# Dashboard_rev2.net
KiCad netlist of a schematic drawn in EAGLE
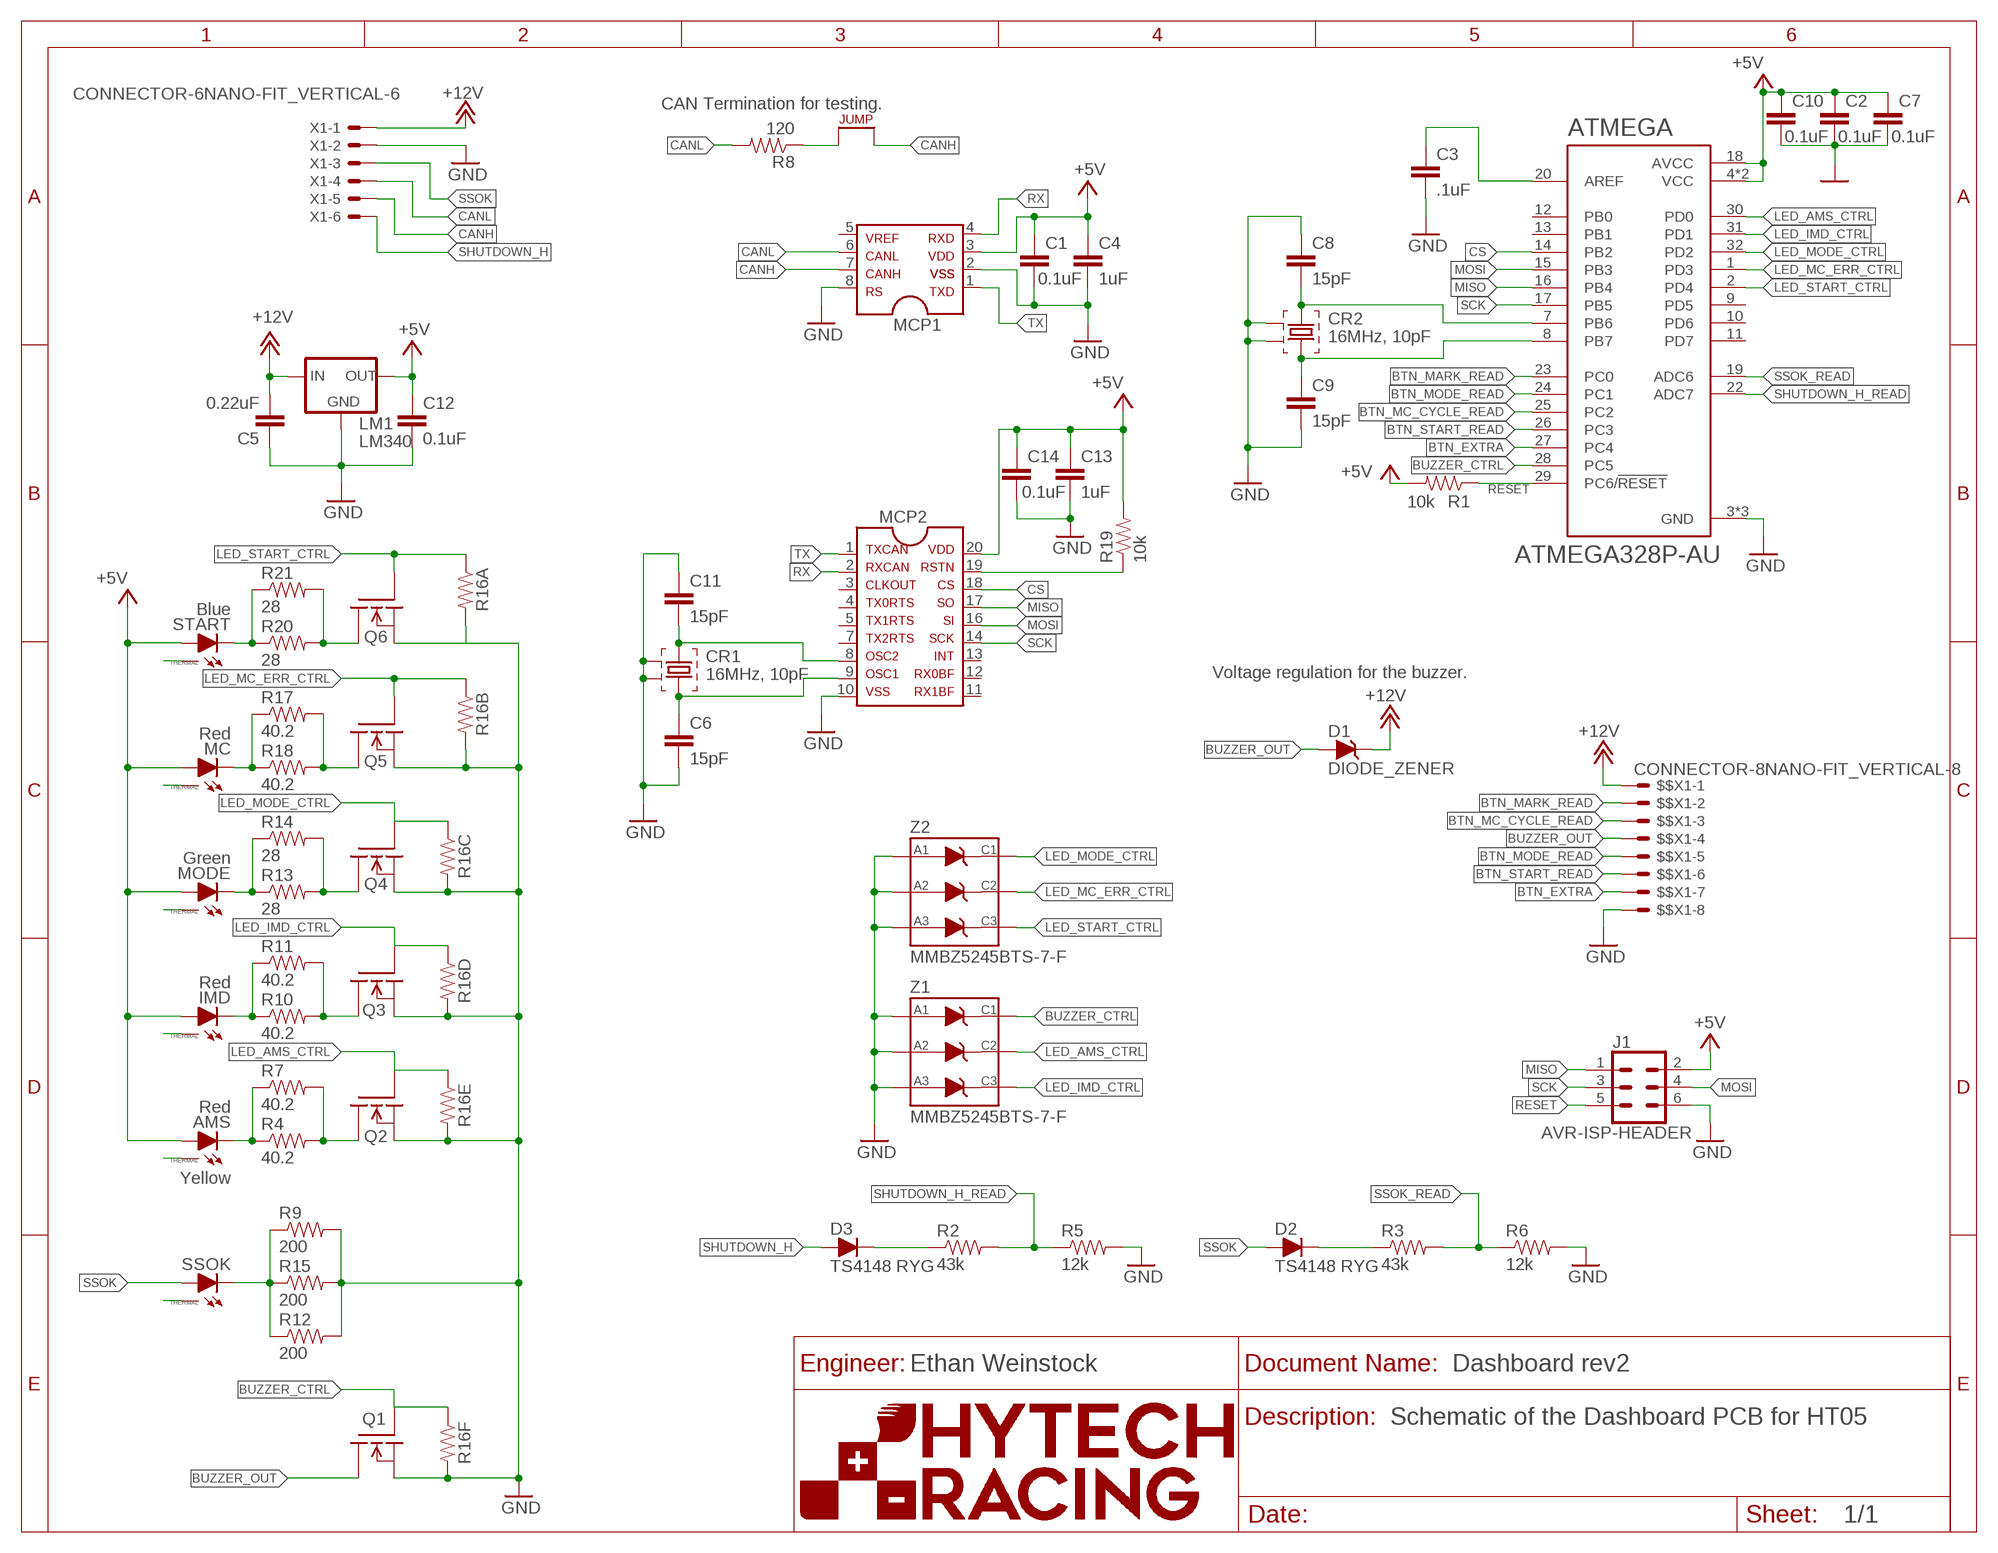
[diagram p0: schematic, sheet 1]

(export (version "E")
  (design (tool "Eeschema 10.0.6"))
  (components
    (comp (ref "$$X1")
      (value "CONNECTOR-8NANO-FIT_VERTICAL-8")
      (footprint "eagle-import:NANO-FIT_VERTICAL-8")
      (libsource (lib "eagle-import") (part "CONNECTOR-8NANO-FIT_VERTICAL-8"))
    )
    (comp (ref "AMS")
      (value "Red")
      (footprint "eagle-import:XP-E2")
      (libsource (lib "eagle-import") (part "XP-E2XP-E2"))
    )
    (comp (ref "ATMEGA")
      (value "ATMEGA328P-AU")
      (footprint "eagle-import:QFP80P900X900X120-32N")
      (fields (field (name "MF") "Microchip"))
      (libsource (lib "eagle-import") (part "ATMEGA328P-AU"))
    )
    (comp (ref "C1")
      (value "0.1uF")
      (footprint "eagle-import:0603-CAP")
      (libsource (lib "eagle-import") (part "CAP0603-CAP"))
    )
    (comp (ref "C2")
      (value "0.1uF")
      (footprint "eagle-import:0603-CAP")
      (libsource (lib "eagle-import") (part "CAP0603-CAP"))
    )
    (comp (ref "C3")
      (value ".1uF")
      (footprint "eagle-import:0603-CAP")
      (libsource (lib "eagle-import") (part "CAP0603-CAP"))
    )
    (comp (ref "C4")
      (value "1uF")
      (footprint "eagle-import:0603-CAP")
      (libsource (lib "eagle-import") (part "CAP0603-CAP"))
    )
    (comp (ref "C5")
      (value "0.22uF")
      (footprint "eagle-import:0603-CAP")
      (libsource (lib "eagle-import") (part "CAP0603-CAP"))
    )
    (comp (ref "C6")
      (value "15pF")
      (footprint "eagle-import:0603-CAP")
      (libsource (lib "eagle-import") (part "CAP0603-CAP"))
    )
    (comp (ref "C7")
      (value "0.1uF")
      (footprint "eagle-import:0603-CAP")
      (libsource (lib "eagle-import") (part "CAP0603-CAP"))
    )
    (comp (ref "C8")
      (value "15pF")
      (footprint "eagle-import:0603-CAP")
      (libsource (lib "eagle-import") (part "CAP0603-CAP"))
    )
    (comp (ref "C9")
      (value "15pF")
      (footprint "eagle-import:0603-CAP")
      (libsource (lib "eagle-import") (part "CAP0603-CAP"))
    )
    (comp (ref "C10")
      (value "0.1uF")
      (footprint "eagle-import:0603-CAP")
      (libsource (lib "eagle-import") (part "CAP0603-CAP"))
    )
    (comp (ref "C11")
      (value "15pF")
      (footprint "eagle-import:0603-CAP")
      (libsource (lib "eagle-import") (part "CAP0603-CAP"))
    )
    (comp (ref "C12")
      (value "0.1uF")
      (footprint "eagle-import:0603-CAP")
      (libsource (lib "eagle-import") (part "CAP0603-CAP"))
    )
    (comp (ref "C13")
      (value "1uF")
      (footprint "eagle-import:0603-CAP")
      (libsource (lib "eagle-import") (part "CAP0603-CAP"))
    )
    (comp (ref "C14")
      (value "0.1uF")
      (footprint "eagle-import:0603-CAP")
      (libsource (lib "eagle-import") (part "CAP0603-CAP"))
    )
    (comp (ref "CR1")
      (value "16MHz, 10pF")
      (footprint "eagle-import:ABM3B")
      (libsource (lib "eagle-import") (part "ABM3B"))
    )
    (comp (ref "CR2")
      (value "16MHz, 10pF")
      (footprint "eagle-import:ABM3B")
      (libsource (lib "eagle-import") (part "ABM3B"))
    )
    (comp (ref "D1")
      (value "DIODE_ZENER")
      (footprint "eagle-import:SOT23")
      (libsource (lib "eagle-import") (part "DIODE_ZENER"))
    )
    (comp (ref "D2")
      (value "TS4148 RYG")
      (footprint "eagle-import:0805_D")
      (libsource (lib "eagle-import") (part "DIODE0805"))
    )
    (comp (ref "D3")
      (value "TS4148 RYG")
      (footprint "eagle-import:0805_D")
      (libsource (lib "eagle-import") (part "DIODE0805"))
    )
    (comp (ref "IMD")
      (value "Red")
      (footprint "eagle-import:XP-E2")
      (libsource (lib "eagle-import") (part "XP-E2XP-E2"))
    )
    (comp (ref "J1")
      (value "AVR-ISP-HEADER")
      (footprint "eagle-import:2X03")
      (libsource (lib "eagle-import") (part "AVR-ISP-HEADER"))
    )
    (comp (ref "J2")
      (value "JUMPER0603")
      (footprint "eagle-import:0603-JUMP")
      (libsource (lib "eagle-import") (part "JUMPER0603"))
    )
    (comp (ref "LM1")
      (value "LM340")
      (footprint "eagle-import:SOT223")
      (libsource (lib "eagle-import") (part "LM340"))
    )
    (comp (ref "MC")
      (value "Red")
      (footprint "eagle-import:XP-E2")
      (libsource (lib "eagle-import") (part "XP-E2XP-E2"))
    )
    (comp (ref "MCP1")
      (value "MCP2551")
      (footprint "eagle-import:SOIC-08")
      (libsource (lib "eagle-import") (part "MCP2551"))
    )
    (comp (ref "MCP2")
      (value "MCP2515TSSOP")
      (footprint "eagle-import:TSSOP-20")
      (libsource (lib "eagle-import") (part "MCP2515TSSOP"))
    )
    (comp (ref "MODE")
      (value "Green")
      (footprint "eagle-import:XP-E2")
      (libsource (lib "eagle-import") (part "XP-E2XP-E2"))
    )
    (comp (ref "Q1")
      (value "DMG3406LSOT")
      (footprint "eagle-import:SOT23")
      (libsource (lib "eagle-import") (part "DMG3406LSOT"))
    )
    (comp (ref "Q2")
      (value "DMG3406LSOT")
      (footprint "eagle-import:SOT23")
      (libsource (lib "eagle-import") (part "DMG3406LSOT"))
    )
    (comp (ref "Q3")
      (value "DMG3406LSOT")
      (footprint "eagle-import:SOT23")
      (libsource (lib "eagle-import") (part "DMG3406LSOT"))
    )
    (comp (ref "Q4")
      (value "DMG3406LSOT")
      (footprint "eagle-import:SOT23")
      (libsource (lib "eagle-import") (part "DMG3406LSOT"))
    )
    (comp (ref "Q5")
      (value "DMG3406LSOT")
      (footprint "eagle-import:SOT23")
      (libsource (lib "eagle-import") (part "DMG3406LSOT"))
    )
    (comp (ref "Q6")
      (value "DMG3406LSOT")
      (footprint "eagle-import:SOT23")
      (libsource (lib "eagle-import") (part "DMG3406LSOT"))
    )
    (comp (ref "R1")
      (value "10k")
      (footprint "eagle-import:0603-RES")
      (libsource (lib "eagle-import") (part "RESISTOR0603"))
    )
    (comp (ref "R2")
      (value "43k")
      (footprint "eagle-import:0603-RES")
      (libsource (lib "eagle-import") (part "RESISTOR0603"))
    )
    (comp (ref "R3")
      (value "43k")
      (footprint "eagle-import:0603-RES")
      (libsource (lib "eagle-import") (part "RESISTOR0603"))
    )
    (comp (ref "R4")
      (value "40.2")
      (footprint "eagle-import:0603-RES")
      (libsource (lib "eagle-import") (part "RESISTOR0603"))
    )
    (comp (ref "R5")
      (value "12k")
      (footprint "eagle-import:0603-RES")
      (libsource (lib "eagle-import") (part "RESISTOR0603"))
    )
    (comp (ref "R6")
      (value "12k")
      (footprint "eagle-import:0603-RES")
      (libsource (lib "eagle-import") (part "RESISTOR0603"))
    )
    (comp (ref "R7")
      (value "40.2")
      (footprint "eagle-import:0603-RES")
      (libsource (lib "eagle-import") (part "RESISTOR0603"))
    )
    (comp (ref "R8")
      (value "120")
      (footprint "eagle-import:0603-RES")
      (libsource (lib "eagle-import") (part "RESISTOR0603-RES"))
    )
    (comp (ref "R9")
      (value "200")
      (footprint "eagle-import:0805")
      (libsource (lib "eagle-import") (part "RESISTOR0805-RES"))
    )
    (comp (ref "R10")
      (value "40.2")
      (footprint "eagle-import:0603-RES")
      (libsource (lib "eagle-import") (part "RESISTOR0603"))
    )
    (comp (ref "R11")
      (value "40.2")
      (footprint "eagle-import:0603-RES")
      (libsource (lib "eagle-import") (part "RESISTOR0603"))
    )
    (comp (ref "R12")
      (value "200")
      (footprint "eagle-import:0805")
      (libsource (lib "eagle-import") (part "RESISTOR0805-RES"))
    )
    (comp (ref "R13")
      (value "28")
      (footprint "eagle-import:0603-RES")
      (libsource (lib "eagle-import") (part "RESISTOR0603"))
    )
    (comp (ref "R14")
      (value "28")
      (footprint "eagle-import:0603-RES")
      (libsource (lib "eagle-import") (part "RESISTOR0603"))
    )
    (comp (ref "R15")
      (value "200")
      (footprint "eagle-import:0805")
      (libsource (lib "eagle-import") (part "RESISTOR0805-RES"))
    )
    (comp (ref "R16")
      (value "10k")
      (footprint "eagle-import:YAG_YC248-M")
      (fields (field (name "MANUFACTURER_PART_NUMBER") "YC248-JR-0710KL"))
      (libsource (lib "eagle-import") (part "YC248-JR-0710KL"))
    )
    (comp (ref "R17")
      (value "40.2")
      (footprint "eagle-import:0603-RES")
      (libsource (lib "eagle-import") (part "RESISTOR0603"))
    )
    (comp (ref "R18")
      (value "40.2")
      (footprint "eagle-import:0603-RES")
      (libsource (lib "eagle-import") (part "RESISTOR0603"))
    )
    (comp (ref "R19")
      (value "10k")
      (footprint "eagle-import:0603-RES")
      (libsource (lib "eagle-import") (part "RESISTOR0603"))
    )
    (comp (ref "R20")
      (value "28")
      (footprint "eagle-import:0603-RES")
      (libsource (lib "eagle-import") (part "RESISTOR0603"))
    )
    (comp (ref "R21")
      (value "28")
      (footprint "eagle-import:0603-RES")
      (libsource (lib "eagle-import") (part "RESISTOR0603"))
    )
    (comp (ref "SSOK")
      (value "Yellow")
      (footprint "eagle-import:XP-E2")
      (libsource (lib "eagle-import") (part "XP-E2XP-E2"))
    )
    (comp (ref "START")
      (value "Blue")
      (footprint "eagle-import:XP-E2")
      (libsource (lib "eagle-import") (part "XP-E2XP-E2"))
    )
    (comp (ref "X1")
      (value "CONNECTOR-6NANO-FIT_VERTICAL-6")
      (footprint "eagle-import:NANO-FIT_VERTICAL-6")
      (libsource (lib "eagle-import") (part "CONNECTOR-6NANO-FIT_VERTICAL-6"))
    )
    (comp (ref "Z1")
      (value "MMBZ5245BTS-7-F")
      (footprint "eagle-import:SOT363")
      (fields (field (name "VOLTAGE") "15V"))
      (libsource (lib "eagle-import") (part "MMBZ5245BTS-7-F"))
    )
    (comp (ref "Z2")
      (value "MMBZ5245BTS-7-F")
      (footprint "eagle-import:SOT363")
      (fields (field (name "VOLTAGE") "15V"))
      (libsource (lib "eagle-import") (part "MMBZ5245BTS-7-F"))
    )
  )
  (nets
    (net (code "1") (name "+5V") (class "Default")
      (node (ref "AMS") (pin "A") (pinfunction "A_A") (pintype "passive"))
      (node (ref "ATMEGA") (pin "18") (pinfunction "AVCC_18") (pintype "power_in"))
      (node (ref "ATMEGA") (pin "4") (pinfunction "VCC_4") (pintype "power_in"))
      (node (ref "ATMEGA") (pin "6") (pinfunction "VCC_6") (pintype "power_in"))
      (node (ref "C1") (pin "1") (pinfunction "1_1") (pintype "passive"))
      (node (ref "C10") (pin "1") (pinfunction "1_1") (pintype "passive"))
      (node (ref "C12") (pin "1") (pinfunction "1_1") (pintype "passive"))
      (node (ref "C13") (pin "1") (pinfunction "1_1") (pintype "passive"))
      (node (ref "C14") (pin "1") (pinfunction "1_1") (pintype "passive"))
      (node (ref "C2") (pin "1") (pinfunction "1_1") (pintype "passive"))
      (node (ref "C4") (pin "1") (pinfunction "1_1") (pintype "passive"))
      (node (ref "C7") (pin "1") (pinfunction "1_1") (pintype "passive"))
      (node (ref "IMD") (pin "A") (pinfunction "A_A") (pintype "passive"))
      (node (ref "J1") (pin "2") (pinfunction "2_2") (pintype "passive"))
      (node (ref "LM1") (pin "3") (pinfunction "OUT_3") (pintype "output"))
      (node (ref "MC") (pin "A") (pinfunction "A_A") (pintype "passive"))
      (node (ref "MCP1") (pin "3") (pinfunction "3_3") (pintype "passive"))
      (node (ref "MCP2") (pin "20") (pinfunction "VDD_20") (pintype "passive"))
      (node (ref "MODE") (pin "A") (pinfunction "A_A") (pintype "passive"))
      (node (ref "R1") (pin "2") (pinfunction "2_2") (pintype "passive"))
      (node (ref "R19") (pin "2") (pinfunction "2_2") (pintype "passive"))
      (node (ref "START") (pin "A") (pinfunction "A_A") (pintype "passive"))
    )
    (net (code "2") (name "+12V") (class "Default")
      (node (ref "$$X1") (pin "P$1") (pinfunction "S_P$1") (pintype "passive"))
      (node (ref "C5") (pin "2") (pinfunction "2_2") (pintype "passive"))
      (node (ref "D1") (pin "3") (pinfunction "C_3") (pintype "passive"))
      (node (ref "LM1") (pin "1") (pinfunction "IN_1") (pintype "input"))
      (node (ref "X1") (pin "P$1") (pinfunction "S_P$1") (pintype "passive"))
    )
    (net (code "3") (name "/THERMAL") (class "Default")
      (node (ref "AMS") (pin "X") (pinfunction "X_X") (pintype "passive"))
      (node (ref "IMD") (pin "X") (pinfunction "X_X") (pintype "passive"))
      (node (ref "MC") (pin "X") (pinfunction "X_X") (pintype "passive"))
      (node (ref "MODE") (pin "X") (pinfunction "X_X") (pintype "passive"))
      (node (ref "SSOK") (pin "X") (pinfunction "X_X") (pintype "passive"))
      (node (ref "START") (pin "X") (pinfunction "X_X") (pintype "passive"))
    )
    (net (code "4") (name "BTN_EXTRA") (class "Default")
      (node (ref "$$X1") (pin "P$7") (pinfunction "S_P$7") (pintype "passive"))
      (node (ref "ATMEGA") (pin "27") (pinfunction "PC4_27") (pintype "bidirectional"))
    )
    (net (code "5") (name "BTN_MARK_READ") (class "Default")
      (node (ref "$$X1") (pin "P$2") (pinfunction "S_P$2") (pintype "passive"))
      (node (ref "ATMEGA") (pin "23") (pinfunction "PC0_23") (pintype "bidirectional"))
    )
    (net (code "6") (name "BTN_MC_CYCLE_READ") (class "Default")
      (node (ref "$$X1") (pin "P$3") (pinfunction "S_P$3") (pintype "passive"))
      (node (ref "ATMEGA") (pin "25") (pinfunction "PC2_25") (pintype "bidirectional"))
    )
    (net (code "7") (name "BTN_MODE_READ") (class "Default")
      (node (ref "$$X1") (pin "P$5") (pinfunction "S_P$5") (pintype "passive"))
      (node (ref "ATMEGA") (pin "24") (pinfunction "PC1_24") (pintype "bidirectional"))
    )
    (net (code "8") (name "BTN_START_READ") (class "Default")
      (node (ref "$$X1") (pin "P$6") (pinfunction "S_P$6") (pintype "passive"))
      (node (ref "ATMEGA") (pin "26") (pinfunction "PC3_26") (pintype "bidirectional"))
    )
    (net (code "9") (name "BUZZER_CTRL") (class "Default")
      (node (ref "ATMEGA") (pin "28") (pinfunction "PC5_28") (pintype "bidirectional"))
      (node (ref "Q1") (pin "1") (pinfunction "G_1") (pintype "passive"))
      (node (ref "R16") (pin "6") (pinfunction "1_6") (pintype "passive"))
      (node (ref "Z1") (pin "P$4") (pinfunction "C1_P$4") (pintype "bidirectional"))
    )
    (net (code "10") (name "BUZZER_OUT") (class "Default")
      (node (ref "$$X1") (pin "P$4") (pinfunction "S_P$4") (pintype "passive"))
      (node (ref "D1") (pin "1") (pinfunction "A_1") (pintype "passive"))
      (node (ref "Q1") (pin "3") (pinfunction "D_3") (pintype "passive"))
    )
    (net (code "11") (name "CANH") (class "Default")
      (node (ref "J2") (pin "2") (pinfunction "P$2_2") (pintype "bidirectional"))
      (node (ref "MCP1") (pin "7") (pinfunction "7_7") (pintype "passive"))
      (node (ref "X1") (pin "P$5") (pinfunction "S_P$5") (pintype "passive"))
    )
    (net (code "12") (name "CANL") (class "Default")
      (node (ref "MCP1") (pin "6") (pinfunction "6_6") (pintype "passive"))
      (node (ref "R8") (pin "2") (pinfunction "2_2") (pintype "passive"))
      (node (ref "X1") (pin "P$4") (pinfunction "S_P$4") (pintype "passive"))
    )
    (net (code "13") (name "CS") (class "Default")
      (node (ref "ATMEGA") (pin "14") (pinfunction "PB2_14") (pintype "bidirectional"))
      (node (ref "MCP2") (pin "18") (pinfunction "CS_18") (pintype "passive"))
    )
    (net (code "14") (name "GND") (class "Default")
      (node (ref "$$X1") (pin "P$8") (pinfunction "S_P$8") (pintype "passive"))
      (node (ref "ATMEGA") (pin "21") (pinfunction "GND_21") (pintype "power_in"))
      (node (ref "ATMEGA") (pin "3") (pinfunction "GND_3") (pintype "power_in"))
      (node (ref "ATMEGA") (pin "5") (pinfunction "GND_5") (pintype "power_in"))
      (node (ref "C1") (pin "2") (pinfunction "2_2") (pintype "passive"))
      (node (ref "C10") (pin "2") (pinfunction "2_2") (pintype "passive"))
      (node (ref "C11") (pin "1") (pinfunction "1_1") (pintype "passive"))
      (node (ref "C12") (pin "2") (pinfunction "2_2") (pintype "passive"))
      (node (ref "C13") (pin "2") (pinfunction "2_2") (pintype "passive"))
      (node (ref "C14") (pin "2") (pinfunction "2_2") (pintype "passive"))
      (node (ref "C2") (pin "2") (pinfunction "2_2") (pintype "passive"))
      (node (ref "C3") (pin "2") (pinfunction "2_2") (pintype "passive"))
      (node (ref "C4") (pin "2") (pinfunction "2_2") (pintype "passive"))
      (node (ref "C5") (pin "1") (pinfunction "1_1") (pintype "passive"))
      (node (ref "C6") (pin "2") (pinfunction "2_2") (pintype "passive"))
      (node (ref "C7") (pin "2") (pinfunction "2_2") (pintype "passive"))
      (node (ref "C8") (pin "1") (pinfunction "1_1") (pintype "passive"))
      (node (ref "C9") (pin "2") (pinfunction "2_2") (pintype "passive"))
      (node (ref "CR1") (pin "GND") (pinfunction "GND_GND") (pintype "passive"))
      (node (ref "CR1") (pin "GND2") (pinfunction "GND2_GND2") (pintype "passive"))
      (node (ref "CR2") (pin "GND") (pinfunction "GND_GND") (pintype "passive"))
      (node (ref "CR2") (pin "GND2") (pinfunction "GND2_GND2") (pintype "passive"))
      (node (ref "J1") (pin "6") (pinfunction "6_6") (pintype "passive"))
      (node (ref "LM1") (pin "2") (pinfunction "GND_2") (pintype "input"))
      (node (ref "LM1") (pin "4") (pinfunction "GND_4") (pintype "input"))
      (node (ref "MCP1") (pin "2") (pinfunction "2_2") (pintype "passive"))
      (node (ref "MCP1") (pin "8") (pinfunction "8_8") (pintype "passive"))
      (node (ref "MCP2") (pin "10") (pinfunction "VSS_10") (pintype "passive"))
      (node (ref "Q1") (pin "2") (pinfunction "S_2") (pintype "passive"))
      (node (ref "Q2") (pin "2") (pinfunction "S_2") (pintype "passive"))
      (node (ref "Q3") (pin "2") (pinfunction "S_2") (pintype "passive"))
      (node (ref "Q4") (pin "2") (pinfunction "S_2") (pintype "passive"))
      (node (ref "Q5") (pin "2") (pinfunction "S_2") (pintype "passive"))
      (node (ref "Q6") (pin "2") (pinfunction "S_2") (pintype "passive"))
      (node (ref "R12") (pin "2") (pinfunction "2_2") (pintype "passive"))
      (node (ref "R15") (pin "2") (pinfunction "2_2") (pintype "passive"))
      (node (ref "R16") (pin "11") (pinfunction "2_11") (pintype "passive"))
      (node (ref "R16") (pin "12") (pinfunction "2_12") (pintype "passive"))
      (node (ref "R16") (pin "13") (pinfunction "2_13") (pintype "passive"))
      (node (ref "R16") (pin "14") (pinfunction "2_14") (pintype "passive"))
      (node (ref "R16") (pin "15") (pinfunction "2_15") (pintype "passive"))
      (node (ref "R16") (pin "16") (pinfunction "2_16") (pintype "passive"))
      (node (ref "R5") (pin "2") (pinfunction "2_2") (pintype "passive"))
      (node (ref "R6") (pin "2") (pinfunction "2_2") (pintype "passive"))
      (node (ref "R9") (pin "2") (pinfunction "2_2") (pintype "passive"))
      (node (ref "X1") (pin "P$2") (pinfunction "S_P$2") (pintype "passive"))
      (node (ref "Z1") (pin "P$1") (pinfunction "A1_P$1") (pintype "bidirectional"))
      (node (ref "Z1") (pin "P$2") (pinfunction "A2_P$2") (pintype "bidirectional"))
      (node (ref "Z1") (pin "P$3") (pinfunction "A3_P$3") (pintype "bidirectional"))
      (node (ref "Z2") (pin "P$1") (pinfunction "A1_P$1") (pintype "bidirectional"))
      (node (ref "Z2") (pin "P$2") (pinfunction "A2_P$2") (pintype "bidirectional"))
      (node (ref "Z2") (pin "P$3") (pinfunction "A3_P$3") (pintype "bidirectional"))
    )
    (net (code "15") (name "LED_AMS_CTRL") (class "Default")
      (node (ref "ATMEGA") (pin "30") (pinfunction "PD0_30") (pintype "bidirectional"))
      (node (ref "Q2") (pin "1") (pinfunction "G_1") (pintype "passive"))
      (node (ref "R16") (pin "5") (pinfunction "1_5") (pintype "passive"))
      (node (ref "Z1") (pin "P$5") (pinfunction "C2_P$5") (pintype "bidirectional"))
    )
    (net (code "16") (name "LED_IMD_CTRL") (class "Default")
      (node (ref "ATMEGA") (pin "31") (pinfunction "PD1_31") (pintype "bidirectional"))
      (node (ref "Q3") (pin "1") (pinfunction "G_1") (pintype "passive"))
      (node (ref "R16") (pin "4") (pinfunction "1_4") (pintype "passive"))
      (node (ref "Z1") (pin "P$6") (pinfunction "C3_P$6") (pintype "bidirectional"))
    )
    (net (code "17") (name "LED_MC_ERR_CTRL") (class "Default")
      (node (ref "ATMEGA") (pin "1") (pinfunction "PD3_1") (pintype "bidirectional"))
      (node (ref "Q5") (pin "1") (pinfunction "G_1") (pintype "passive"))
      (node (ref "R16") (pin "2") (pinfunction "1_2") (pintype "passive"))
      (node (ref "Z2") (pin "P$5") (pinfunction "C2_P$5") (pintype "bidirectional"))
    )
    (net (code "18") (name "LED_MODE_CTRL") (class "Default")
      (node (ref "ATMEGA") (pin "32") (pinfunction "PD2_32") (pintype "bidirectional"))
      (node (ref "Q4") (pin "1") (pinfunction "G_1") (pintype "passive"))
      (node (ref "R16") (pin "3") (pinfunction "1_3") (pintype "passive"))
      (node (ref "Z2") (pin "P$4") (pinfunction "C1_P$4") (pintype "bidirectional"))
    )
    (net (code "19") (name "LED_START_CTRL") (class "Default")
      (node (ref "ATMEGA") (pin "2") (pinfunction "PD4_2") (pintype "bidirectional"))
      (node (ref "Q6") (pin "1") (pinfunction "G_1") (pintype "passive"))
      (node (ref "R16") (pin "1") (pinfunction "1_1") (pintype "passive"))
      (node (ref "Z2") (pin "P$6") (pinfunction "C3_P$6") (pintype "bidirectional"))
    )
    (net (code "20") (name "MISO") (class "Default")
      (node (ref "ATMEGA") (pin "16") (pinfunction "PB4_16") (pintype "bidirectional"))
      (node (ref "J1") (pin "1") (pinfunction "1_1") (pintype "passive"))
      (node (ref "MCP2") (pin "17") (pinfunction "SO_17") (pintype "passive"))
    )
    (net (code "21") (name "MOSI") (class "Default")
      (node (ref "ATMEGA") (pin "15") (pinfunction "PB3_15") (pintype "bidirectional"))
      (node (ref "J1") (pin "4") (pinfunction "4_4") (pintype "passive"))
      (node (ref "MCP2") (pin "16") (pinfunction "SI_16") (pintype "passive"))
    )
    (net (code "22") (name "Net-(AMS-PadC)") (class "Default")
      (node (ref "AMS") (pin "C") (pinfunction "C_C") (pintype "passive"))
      (node (ref "R4") (pin "1") (pinfunction "1_1") (pintype "passive"))
      (node (ref "R7") (pin "1") (pinfunction "1_1") (pintype "passive"))
    )
    (net (code "23") (name "Net-(ATMEGA-AREF)") (class "Default")
      (node (ref "ATMEGA") (pin "20") (pinfunction "AREF_20") (pintype "input"))
      (node (ref "C3") (pin "1") (pinfunction "1_1") (pintype "passive"))
    )
    (net (code "24") (name "Net-(ATMEGA-PB6)") (class "Default")
      (node (ref "ATMEGA") (pin "7") (pinfunction "PB6_7") (pintype "bidirectional"))
      (node (ref "C8") (pin "2") (pinfunction "2_2") (pintype "passive"))
      (node (ref "CR2") (pin "1") (pinfunction "1_1") (pintype "passive"))
    )
    (net (code "25") (name "Net-(ATMEGA-PB7)") (class "Default")
      (node (ref "ATMEGA") (pin "8") (pinfunction "PB7_8") (pintype "bidirectional"))
      (node (ref "C9") (pin "1") (pinfunction "1_1") (pintype "passive"))
      (node (ref "CR2") (pin "3") (pinfunction "3_3") (pintype "passive"))
    )
    (net (code "26") (name "Net-(D2-PadC)") (class "Default")
      (node (ref "D2") (pin "C") (pinfunction "C_C") (pintype "passive"))
      (node (ref "R3") (pin "1") (pinfunction "1_1") (pintype "passive"))
    )
    (net (code "27") (name "Net-(D3-PadC)") (class "Default")
      (node (ref "D3") (pin "C") (pinfunction "C_C") (pintype "passive"))
      (node (ref "R2") (pin "1") (pinfunction "1_1") (pintype "passive"))
    )
    (net (code "28") (name "Net-(IMD-PadC)") (class "Default")
      (node (ref "IMD") (pin "C") (pinfunction "C_C") (pintype "passive"))
      (node (ref "R10") (pin "1") (pinfunction "1_1") (pintype "passive"))
      (node (ref "R11") (pin "1") (pinfunction "1_1") (pintype "passive"))
    )
    (net (code "29") (name "Net-(J2-P$1)") (class "Default")
      (node (ref "J2") (pin "1") (pinfunction "P$1_1") (pintype "bidirectional"))
      (node (ref "R8") (pin "1") (pinfunction "1_1") (pintype "passive"))
    )
    (net (code "30") (name "Net-(MC-PadC)") (class "Default")
      (node (ref "MC") (pin "C") (pinfunction "C_C") (pintype "passive"))
      (node (ref "R17") (pin "1") (pinfunction "1_1") (pintype "passive"))
      (node (ref "R18") (pin "1") (pinfunction "1_1") (pintype "passive"))
    )
    (net (code "31") (name "Net-(MCP2-OSC1)") (class "Default")
      (node (ref "C6") (pin "1") (pinfunction "1_1") (pintype "passive"))
      (node (ref "CR1") (pin "3") (pinfunction "3_3") (pintype "passive"))
      (node (ref "MCP2") (pin "9") (pinfunction "OSC1_9") (pintype "passive"))
    )
    (net (code "32") (name "Net-(MCP2-OSC2)") (class "Default")
      (node (ref "C11") (pin "2") (pinfunction "2_2") (pintype "passive"))
      (node (ref "CR1") (pin "1") (pinfunction "1_1") (pintype "passive"))
      (node (ref "MCP2") (pin "8") (pinfunction "OSC2_8") (pintype "passive"))
    )
    (net (code "33") (name "Net-(MCP2-RSTN)") (class "Default")
      (node (ref "MCP2") (pin "19") (pinfunction "RSTN_19") (pintype "passive"))
      (node (ref "R19") (pin "1") (pinfunction "1_1") (pintype "passive"))
    )
    (net (code "34") (name "Net-(MODE-PadC)") (class "Default")
      (node (ref "MODE") (pin "C") (pinfunction "C_C") (pintype "passive"))
      (node (ref "R13") (pin "1") (pinfunction "1_1") (pintype "passive"))
      (node (ref "R14") (pin "1") (pinfunction "1_1") (pintype "passive"))
    )
    (net (code "35") (name "Net-(Q2-D)") (class "Default")
      (node (ref "Q2") (pin "3") (pinfunction "D_3") (pintype "passive"))
      (node (ref "R4") (pin "2") (pinfunction "2_2") (pintype "passive"))
      (node (ref "R7") (pin "2") (pinfunction "2_2") (pintype "passive"))
    )
    (net (code "36") (name "Net-(Q3-D)") (class "Default")
      (node (ref "Q3") (pin "3") (pinfunction "D_3") (pintype "passive"))
      (node (ref "R10") (pin "2") (pinfunction "2_2") (pintype "passive"))
      (node (ref "R11") (pin "2") (pinfunction "2_2") (pintype "passive"))
    )
    (net (code "37") (name "Net-(Q4-D)") (class "Default")
      (node (ref "Q4") (pin "3") (pinfunction "D_3") (pintype "passive"))
      (node (ref "R13") (pin "2") (pinfunction "2_2") (pintype "passive"))
      (node (ref "R14") (pin "2") (pinfunction "2_2") (pintype "passive"))
    )
    (net (code "38") (name "Net-(Q5-D)") (class "Default")
      (node (ref "Q5") (pin "3") (pinfunction "D_3") (pintype "passive"))
      (node (ref "R17") (pin "2") (pinfunction "2_2") (pintype "passive"))
      (node (ref "R18") (pin "2") (pinfunction "2_2") (pintype "passive"))
    )
    (net (code "39") (name "Net-(Q6-D)") (class "Default")
      (node (ref "Q6") (pin "3") (pinfunction "D_3") (pintype "passive"))
      (node (ref "R20") (pin "2") (pinfunction "2_2") (pintype "passive"))
      (node (ref "R21") (pin "2") (pinfunction "2_2") (pintype "passive"))
    )
    (net (code "40") (name "Net-(R12-Pad1)") (class "Default")
      (node (ref "R12") (pin "1") (pinfunction "1_1") (pintype "passive"))
      (node (ref "R15") (pin "1") (pinfunction "1_1") (pintype "passive"))
      (node (ref "R9") (pin "1") (pinfunction "1_1") (pintype "passive"))
      (node (ref "SSOK") (pin "C") (pinfunction "C_C") (pintype "passive"))
    )
    (net (code "41") (name "Net-(R20-Pad1)") (class "Default")
      (node (ref "R20") (pin "1") (pinfunction "1_1") (pintype "passive"))
      (node (ref "R21") (pin "1") (pinfunction "1_1") (pintype "passive"))
      (node (ref "START") (pin "C") (pinfunction "C_C") (pintype "passive"))
    )
    (net (code "42") (name "RESET") (class "Default")
      (node (ref "ATMEGA") (pin "29") (pinfunction "PC6/~{RESET}_29") (pintype "bidirectional"))
      (node (ref "J1") (pin "5") (pinfunction "5_5") (pintype "passive"))
      (node (ref "R1") (pin "1") (pinfunction "1_1") (pintype "passive"))
    )
    (net (code "43") (name "RX") (class "Default")
      (node (ref "MCP1") (pin "4") (pinfunction "4_4") (pintype "passive"))
      (node (ref "MCP2") (pin "2") (pinfunction "RXCAN_2") (pintype "passive"))
    )
    (net (code "44") (name "SCK") (class "Default")
      (node (ref "ATMEGA") (pin "17") (pinfunction "PB5_17") (pintype "bidirectional"))
      (node (ref "J1") (pin "3") (pinfunction "3_3") (pintype "passive"))
      (node (ref "MCP2") (pin "14") (pinfunction "SCK_14") (pintype "passive"))
    )
    (net (code "45") (name "SHUTDOWN_H") (class "Default")
      (node (ref "D3") (pin "A") (pinfunction "A_A") (pintype "passive"))
      (node (ref "X1") (pin "P$6") (pinfunction "S_P$6") (pintype "passive"))
    )
    (net (code "46") (name "SHUTDOWN_H_READ") (class "Default")
      (node (ref "ATMEGA") (pin "22") (pinfunction "ADC7_22") (pintype "bidirectional"))
      (node (ref "R2") (pin "2") (pinfunction "2_2") (pintype "passive"))
      (node (ref "R5") (pin "1") (pinfunction "1_1") (pintype "passive"))
    )
    (net (code "47") (name "SSOK") (class "Default")
      (node (ref "D2") (pin "A") (pinfunction "A_A") (pintype "passive"))
      (node (ref "SSOK") (pin "A") (pinfunction "A_A") (pintype "passive"))
      (node (ref "X1") (pin "P$3") (pinfunction "S_P$3") (pintype "passive"))
    )
    (net (code "48") (name "SSOK_READ") (class "Default")
      (node (ref "ATMEGA") (pin "19") (pinfunction "ADC6_19") (pintype "bidirectional"))
      (node (ref "R3") (pin "2") (pinfunction "2_2") (pintype "passive"))
      (node (ref "R6") (pin "1") (pinfunction "1_1") (pintype "passive"))
    )
    (net (code "49") (name "TX") (class "Default")
      (node (ref "MCP1") (pin "1") (pinfunction "1_1") (pintype "passive"))
      (node (ref "MCP2") (pin "1") (pinfunction "TXCAN_1") (pintype "passive"))
    )
    (net (code "50") (name "unconnected-(ATMEGA-PB0-Pad12)") (class "Default")
      (node (ref "ATMEGA") (pin "12") (pinfunction "PB0_12") (pintype "bidirectional"))
    )
    (net (code "51") (name "unconnected-(ATMEGA-PB1-Pad13)") (class "Default")
      (node (ref "ATMEGA") (pin "13") (pinfunction "PB1_13") (pintype "bidirectional"))
    )
    (net (code "52") (name "unconnected-(ATMEGA-PD5-Pad9)") (class "Default")
      (node (ref "ATMEGA") (pin "9") (pinfunction "PD5_9") (pintype "bidirectional"))
    )
    (net (code "53") (name "unconnected-(ATMEGA-PD6-Pad10)") (class "Default")
      (node (ref "ATMEGA") (pin "10") (pinfunction "PD6_10") (pintype "bidirectional"))
    )
    (net (code "54") (name "unconnected-(ATMEGA-PD7-Pad11)") (class "Default")
      (node (ref "ATMEGA") (pin "11") (pinfunction "PD7_11") (pintype "bidirectional"))
    )
    (net (code "55") (name "unconnected-(MCP1-Pad5)") (class "Default")
      (node (ref "MCP1") (pin "5") (pinfunction "5_5") (pintype "passive"))
    )
    (net (code "56") (name "unconnected-(MCP2-CLKOUT-Pad3)") (class "Default")
      (node (ref "MCP2") (pin "3") (pinfunction "CLKOUT_3") (pintype "passive"))
    )
    (net (code "57") (name "unconnected-(MCP2-INT-Pad13)") (class "Default")
      (node (ref "MCP2") (pin "13") (pinfunction "INT_13") (pintype "passive"))
    )
    (net (code "58") (name "unconnected-(MCP2-RX0BF-Pad12)") (class "Default")
      (node (ref "MCP2") (pin "12") (pinfunction "RX0BF_12") (pintype "passive"))
    )
    (net (code "59") (name "unconnected-(MCP2-RX1BF-Pad11)") (class "Default")
      (node (ref "MCP2") (pin "11") (pinfunction "RX1BF_11") (pintype "passive"))
    )
    (net (code "60") (name "unconnected-(MCP2-TX0RTS-Pad4)") (class "Default")
      (node (ref "MCP2") (pin "4") (pinfunction "TX0RTS_4") (pintype "passive"))
    )
    (net (code "61") (name "unconnected-(MCP2-TX1RTS-Pad5)") (class "Default")
      (node (ref "MCP2") (pin "5") (pinfunction "TX1RTS_5") (pintype "passive"))
    )
    (net (code "62") (name "unconnected-(MCP2-TX2RTS-Pad7)") (class "Default")
      (node (ref "MCP2") (pin "7") (pinfunction "TX2RTS_7") (pintype "passive"))
    )
  )
)
